# Ethernet.net
KiCad netlist of a schematic drawn in Altium Designer
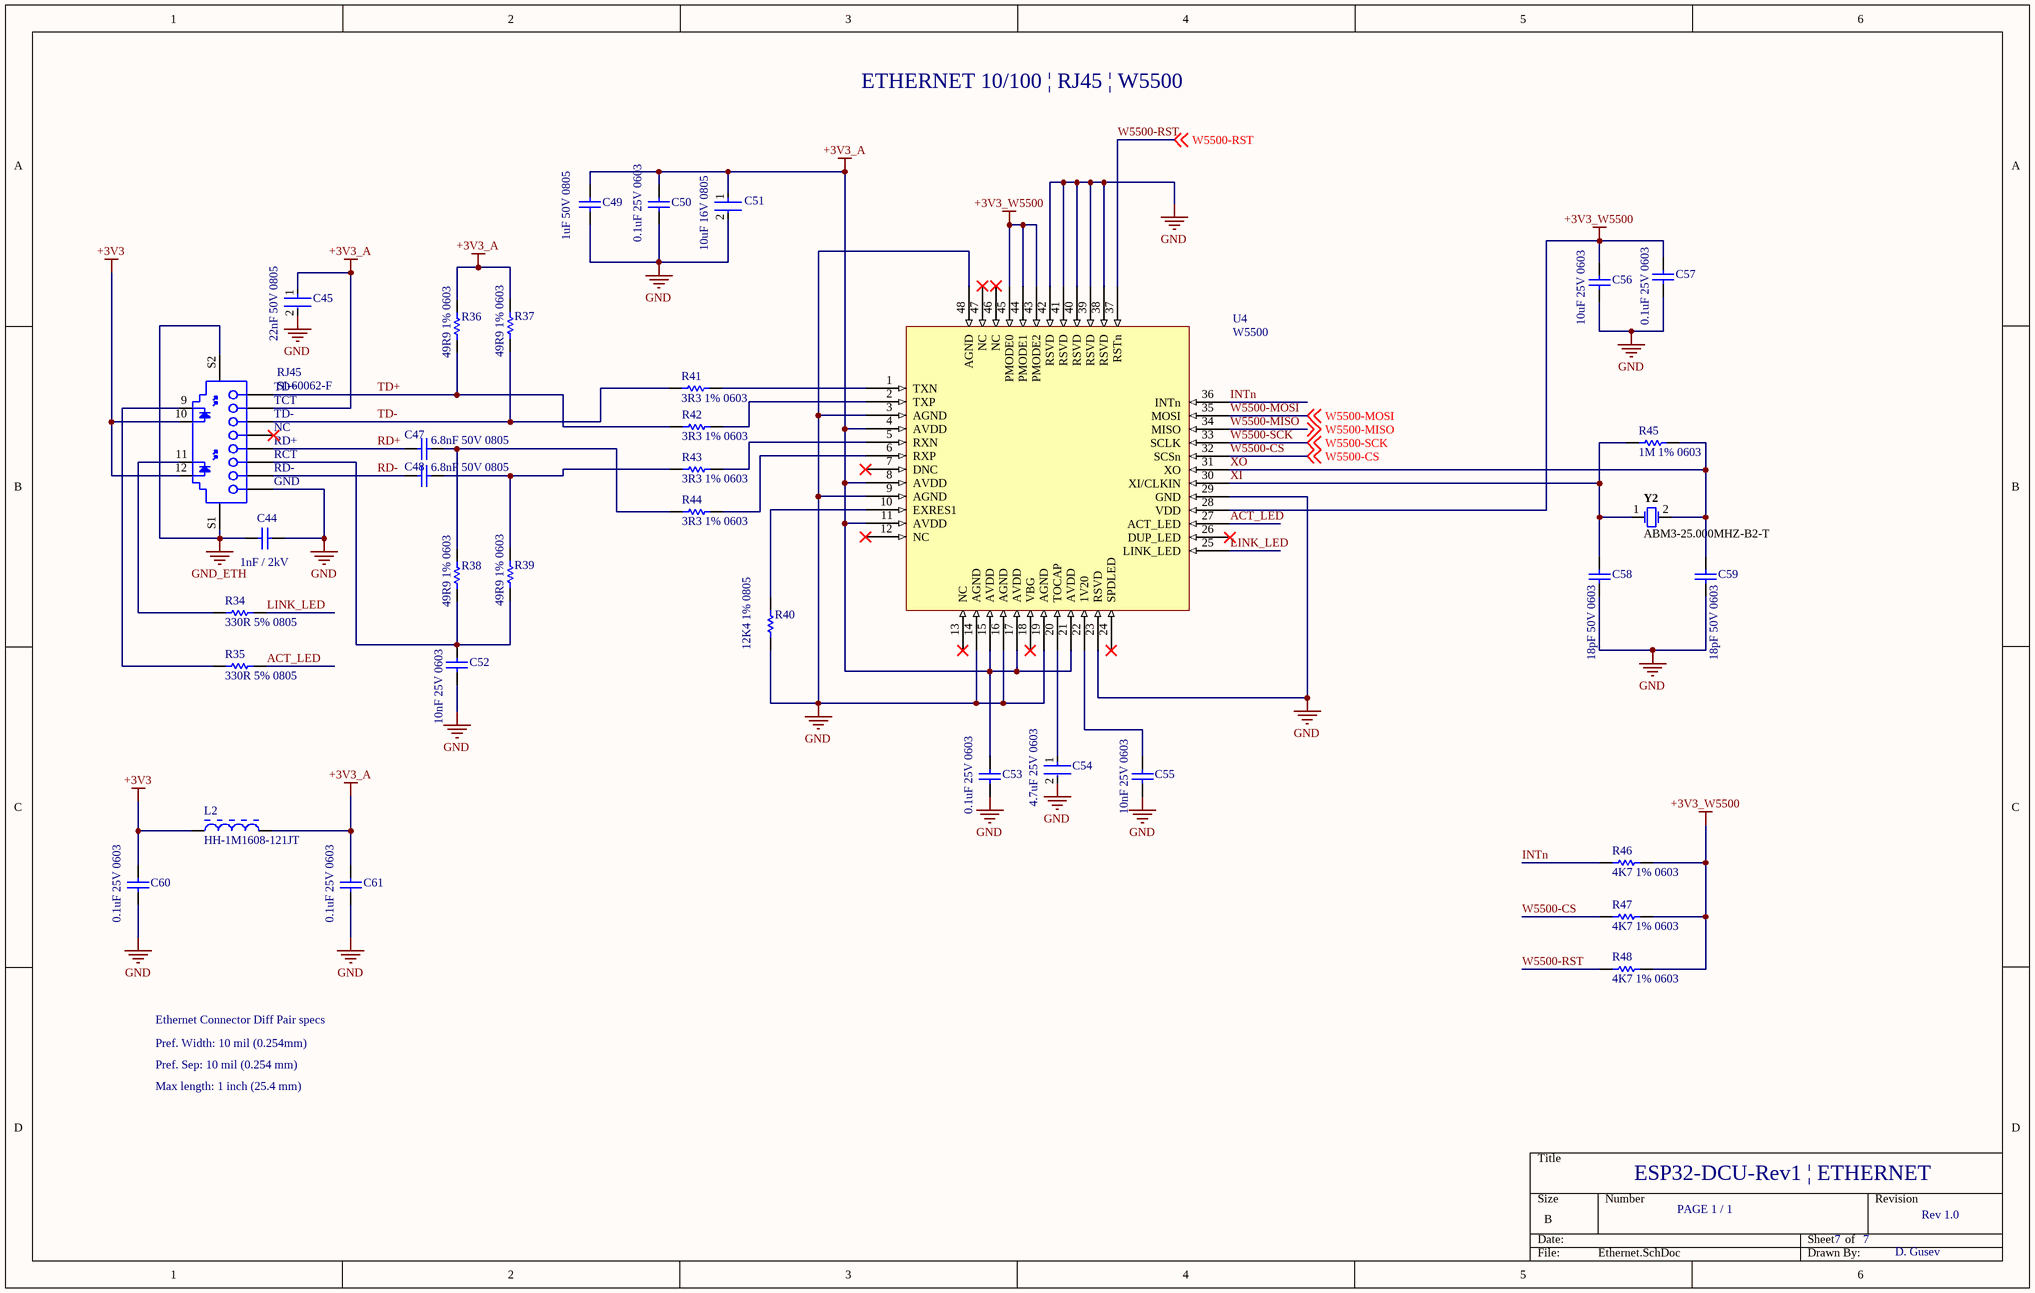
[diagram p0: Ethernet.SchDoc]

(export (version "E")
  (design (tool "Eeschema 10.0.6"))
  (components
    (comp (ref "C44")
      (value "1nF / 2kV")
      (footprint "CAPC4532X155X60LL30T35")
      (description "Chip Capacitor, 1000 pF, +/- 10%, 2000 V, -55 to 125 degC, 1812 (4532 Metric), RoHS, Tape and Reel")
      (fields (field (name "MANUFACTURER") "Kemet") (field (name "TOLERANCE") "±10%"))
      (libsource (lib "Altium Content Vault") (part "CAP-NP-2"))
    )
    (comp (ref "C45")
      (value "22nF 50V 0805")
      (footprint "FP-CL21-IPC_A")
      (description "CL21 Series 0805 22nF 50V ±10% Tolerance X7R Multilayer Ceramic Chip Capacitor")
      (fields (field (name "TOLERANCE") "10%") (field (name "VOLTAGE") "50V"))
      (libsource (lib "Altium Content Vault") (part "b4654b650e69147ec39a6b967a45e02"))
    )
    (comp (ref "C47")
      (value "6.8nF 50V 0805")
      (footprint "CAPC2013X94X50NL20T25")
      (fields
        (field (name "MANUFACTURER") "AVX Interconnect / Elco")
        (field (name "PART NUMBER") "08055C682KAT2A")
      )
      (libsource (lib "Altium Content Vault") (part "CAP"))
    )
    (comp (ref "C48")
      (value "6.8nF 50V 0805")
      (footprint "CAPC2013X94X50NL20T25")
      (fields
        (field (name "MANUFACTURER") "AVX Interconnect / Elco")
        (field (name "PART NUMBER") "08055C682KAT2A")
      )
      (libsource (lib "Altium Content Vault") (part "CAP"))
    )
    (comp (ref "C49")
      (value "1uF 50V 0805")
      (footprint "CAPC2013X135X45LL10T25")
      (fields (field (name "MANUFACTURER") "Murata") (field (name "PART NUMBER") "GRM21BR71H105KA12L"))
      (libsource (lib "Altium Content Vault") (part "CAP"))
    )
    (comp (ref "C50")
      (value "0.1uF 25V 0603")
      (footprint "CAPC1608X90X35LL10T15")
      (fields (field (name "PART NUMBER") "GRM188R71E104KA01D") (field (name "MANUFACTURER") "Murata"))
      (libsource (lib "Altium Content Vault") (part "CAP"))
    )
    (comp (ref "C51")
      (value "10uF 16V 0805")
      (footprint "FP-GRM21B-0_1-IPC_C")
      (description "Chip Multilayer Ceramic Capacitors for General Purpose, 0805, 10uF, X5R, 15%, 10%, 16V")
      (fields (field (name "TOLERANCE") "10%") (field (name "VOLTAGE") "16V"))
      (libsource (lib "Altium Content Vault") (part "b4654b650e69147ec39a6b967a45e02"))
    )
    (comp (ref "C52")
      (value "10nF 25V 0603")
      (footprint "CAPC1608X90X35NL15T15")
      (fields
        (field (name "PART NUMBER") "06033C103KAT2A")
        (field (name "MANUFACTURER") "AVX Interconnect / Elco")
      )
      (libsource (lib "Altium Content Vault") (part "CAP"))
    )
    (comp (ref "C53")
      (value "0.1uF 25V 0603")
      (footprint "CAPC1608X90X35LL10T15")
      (fields (field (name "PART NUMBER") "GRM188R71E104KA01D") (field (name "MANUFACTURER") "Murata"))
      (libsource (lib "Altium Content Vault") (part "CAP"))
    )
    (comp (ref "C54")
      (value "4.7uF 25V 0603")
      (footprint "FP-GRM188-0_15-IPC_C")
      (description "Chip Multilayer Ceramic Capacitors for General Purpose, 0603, 4.7uF, X5R, 15%, 10%, 25V")
      (fields (field (name "VOLTAGE") "25V") (field (name "TOLERANCE") "10%"))
      (libsource (lib "Altium Content Vault") (part "02cd4be3c70576c341d710602a673aa"))
    )
    (comp (ref "C55")
      (value "10nF 25V 0603")
      (footprint "CAPC1608X90X35NL15T15")
      (fields
        (field (name "PART NUMBER") "06033C103KAT2A")
        (field (name "MANUFACTURER") "AVX Interconnect / Elco")
      )
      (libsource (lib "Altium Content Vault") (part "CAP"))
    )
    (comp (ref "C56")
      (value "10uF 25V 0603")
      (footprint "CAPC1608X100X20VL10T10")
      (description "Chip Capacitor, 10 uF, +/- 20%, 25 V, -55 to 85 degC, 0603 (1608 Metric), RoHS, Tape and Reel")
      (fields (field (name "MANUFACTURER") "TDK") (field (name "TOLERANCE") "±20%"))
      (libsource (lib "Altium Content Vault") (part "CAP-NP-2"))
    )
    (comp (ref "C57")
      (value "0.1uF 25V 0603")
      (footprint "CAPC1608X90X35LL10T15")
      (fields (field (name "PART NUMBER") "GRM188R71E104KA01D") (field (name "MANUFACTURER") "Murata"))
      (libsource (lib "Altium Content Vault") (part "CAP"))
    )
    (comp (ref "C58")
      (value "18pF 50V 0603")
      (footprint "CAPC1608X90X40LL10T20")
      (description "Chip Capacitor, 18 pF, +/- 5%, 50 V, -55 to 125 degC, 0603 (1608 Metric), RoHS, Tape and Reel")
      (fields (field (name "TOLERANCE") "1%"))
      (libsource (lib "Altium Content Vault") (part "CAP-NP-2"))
    )
    (comp (ref "C59")
      (value "18pF 50V 0603")
      (footprint "CAPC1608X90X40LL10T20")
      (description "Chip Capacitor, 18 pF, +/- 5%, 50 V, -55 to 125 degC, 0603 (1608 Metric), RoHS, Tape and Reel")
      (fields (field (name "TOLERANCE") "1%"))
      (libsource (lib "Altium Content Vault") (part "CAP-NP-2"))
    )
    (comp (ref "C60")
      (value "0.1uF 25V 0603")
      (footprint "CAPC1608X90X35LL10T15")
      (fields (field (name "PART NUMBER") "GRM188R71E104KA01D") (field (name "MANUFACTURER") "Murata"))
      (libsource (lib "Altium Content Vault") (part "CAP"))
    )
    (comp (ref "C61")
      (value "0.1uF 25V 0603")
      (footprint "CAPC1608X90X35LL10T15")
      (fields (field (name "PART NUMBER") "GRM188R71E104KA01D") (field (name "MANUFACTURER") "Murata"))
      (libsource (lib "Altium Content Vault") (part "CAP"))
    )
    (comp (ref "L2")
      (value "HH-1M1608-121JT")
      (footprint "CTC-1608_L")
      (description "Chip Ferrite Bead, 0.14 Ohm, 1.1 A, -55 to 125 degC, 2-Pin SMD, RoHS, Tape and Reel")
      (fields (field (name "MANUFACTURER") "CTC Coils") (field (name "PARTNUMBER") "HH-1M1608"))
      (libsource (lib "Altium Content Vault") (part "IND-FB-2"))
    )
    (comp (ref "R34")
      (value "330R 5% 0805")
      (footprint "RESC2013X60X35LL10T20")
      (description "Chip Resistor, 330 Ohm, +/- 1%, 125 mW, -55 to 155 degC, 0805 (2012 Metric), RoHS, Tape and Reel")
      (fields (field (name "MANUFACTURER") "Yageo") (field (name "TOLERANCE") "1%"))
      (libsource (lib "Altium Content Vault") (part "RES-2"))
    )
    (comp (ref "R35")
      (value "330R 5% 0805")
      (footprint "RESC2013X60X35LL10T20")
      (description "Chip Resistor, 330 Ohm, +/- 1%, 125 mW, -55 to 155 degC, 0805 (2012 Metric), RoHS, Tape and Reel")
      (fields (field (name "MANUFACTURER") "Yageo") (field (name "TOLERANCE") "1%"))
      (libsource (lib "Altium Content Vault") (part "RES-2"))
    )
    (comp (ref "R36")
      (value "49R9 1% 0603")
      (footprint "RESC1608X55X25NL10T15")
      (libsource (lib "Altium Content Vault") (part "RES-2"))
    )
    (comp (ref "R37")
      (value "49R9 1% 0603")
      (footprint "RESC1608X55X25NL10T15")
      (libsource (lib "Altium Content Vault") (part "RES-2"))
    )
    (comp (ref "R38")
      (value "49R9 1% 0603")
      (footprint "RESC1608X55X25NL10T15")
      (libsource (lib "Altium Content Vault") (part "RES-2"))
    )
    (comp (ref "R39")
      (value "49R9 1% 0603")
      (footprint "RESC1608X55X25NL10T15")
      (libsource (lib "Altium Content Vault") (part "RES-2"))
    )
    (comp (ref "R40")
      (value "12K4 1% 0805")
      (footprint "RESC2013X60X35NL10T20")
      (fields (field (name "PART NUMBER") "RC0805FR-0712K4L") (field (name "MANUFACTURER") "Yageo"))
      (libsource (lib "Altium Content Vault") (part "RES"))
    )
    (comp (ref "R41")
      (value "3R3 1% 0603")
      (footprint "RESC1608X55X25ML10T15")
      (fields (field (name "PART NUMBER") "RC0603JR-073R3L") (field (name "MANUFACTURER") "Yageo"))
      (libsource (lib "Altium Content Vault") (part "RES"))
    )
    (comp (ref "R42")
      (value "3R3 1% 0603")
      (footprint "RESC1608X55X25ML10T15")
      (fields (field (name "PART NUMBER") "RC0603JR-073R3L") (field (name "MANUFACTURER") "Yageo"))
      (libsource (lib "Altium Content Vault") (part "RES"))
    )
    (comp (ref "R43")
      (value "3R3 1% 0603")
      (footprint "RESC1608X55X25ML10T15")
      (fields (field (name "PART NUMBER") "RC0603JR-073R3L") (field (name "MANUFACTURER") "Yageo"))
      (libsource (lib "Altium Content Vault") (part "RES"))
    )
    (comp (ref "R44")
      (value "3R3 1% 0603")
      (footprint "RESC1608X55X25ML10T15")
      (fields (field (name "PART NUMBER") "RC0603JR-073R3L") (field (name "MANUFACTURER") "Yageo"))
      (libsource (lib "Altium Content Vault") (part "RES"))
    )
    (comp (ref "R45")
      (value "1M 1% 0603")
      (footprint "RESC1608X55X25LL10T15")
      (fields (field (name "MANUFACTURER") "Yageo") (field (name "PART NUMBER") "AC0603FR-071ML"))
      (libsource (lib "Altium Content Vault") (part "RES"))
    )
    (comp (ref "R46")
      (value "4K7 1% 0603")
      (footprint "RESC1608X55X25LL10T15")
      (description "Chip Resistor, 4.7 KOhm, +/- 1%, 0.1 W, -55 to 155 degC, 0603 (1608 Metric), RoHS, Tape and Reel")
      (fields (field (name "MANUFACTURER") "Yageo") (field (name "TOLERANCE") "1%"))
      (libsource (lib "Altium Content Vault") (part "RES-2"))
    )
    (comp (ref "R47")
      (value "4K7 1% 0603")
      (footprint "RESC1608X55X25LL10T15")
      (description "Chip Resistor, 4.7 KOhm, +/- 1%, 0.1 W, -55 to 155 degC, 0603 (1608 Metric), RoHS, Tape and Reel")
      (fields (field (name "MANUFACTURER") "Yageo") (field (name "TOLERANCE") "1%"))
      (libsource (lib "Altium Content Vault") (part "RES-2"))
    )
    (comp (ref "R48")
      (value "4K7 1% 0603")
      (footprint "RESC1608X55X25LL10T15")
      (description "Chip Resistor, 4.7 KOhm, +/- 1%, 0.1 W, -55 to 155 degC, 0603 (1608 Metric), RoHS, Tape and Reel")
      (fields (field (name "MANUFACTURER") "Yageo") (field (name "TOLERANCE") "1%"))
      (libsource (lib "Altium Content Vault") (part "RES-2"))
    )
    (comp (ref "RJ45")
      (value "SI-60062-F")
      (footprint "BELF-SI-60062-F_V")
      (description "1 Port RJ45 Magjack Connector with Yellow and Green LED, 10/100 Base-T, 12-Pin THD, RoHS, Tray")
      (fields (field (name "MANUFACTURER") "Bel Fuse"))
      (libsource (lib "Altium Content Vault") (part "RJ45-12-2SHLD"))
    )
    (comp (ref "U4")
      (value "W5500")
      (footprint "W5500")
      (description "W5500 10/100 ETHERNET")
      (libsource (lib "ESP32-DCU-Rev1") (part "W5500"))
    )
    (comp (ref "Y2")
      (value "ABM3-25.000MHZ-B2-T")
      (footprint "ABRA-ABM3_V")
      (description "Miniature Ceramic Crystal, 25 MHz, +/- 20 ppm, -20 to 70 degC, 2-Pin SMD, RoHS, Tape and Reel")
      (fields (field (name "TOLERANCE") "20PPM") (field (name "MANUFACTURER") "ABRACON"))
      (libsource (lib "Altium Content Vault") (part "XTAL-1-2-2"))
    )
  )
  (nets
    (net (code "1") (name "+3V3") (class "Default")
      (node (ref "C60") (pin "2") (pinfunction "2_2") (pintype "passive"))
      (node (ref "L2") (pin "1") (pinfunction "1_1") (pintype "passive"))
      (node (ref "RJ45") (pin "10") (pinfunction "10_10") (pintype "passive"))
      (node (ref "RJ45") (pin "12") (pinfunction "12_12") (pintype "passive"))
    )
    (net (code "2") (name "+3V3_A") (class "Default")
      (node (ref "C45") (pin "1") (pinfunction "1_1") (pintype "passive"))
      (node (ref "C49") (pin "2") (pinfunction "2_2") (pintype "passive"))
      (node (ref "C50") (pin "2") (pinfunction "2_2") (pintype "passive"))
      (node (ref "C51") (pin "1") (pinfunction "1_1") (pintype "passive"))
      (node (ref "C53") (pin "2") (pinfunction "2_2") (pintype "passive"))
      (node (ref "C61") (pin "2") (pinfunction "2_2") (pintype "passive"))
      (node (ref "L2") (pin "2") (pinfunction "2_2") (pintype "passive"))
      (node (ref "R36") (pin "2") (pinfunction "2_2") (pintype "passive"))
      (node (ref "R37") (pin "2") (pinfunction "2_2") (pintype "passive"))
      (node (ref "RJ45") (pin "2") (pinfunction "TCT_2") (pintype "passive"))
      (node (ref "U4") (pin "11") (pinfunction "AVDD_11") (pintype "input"))
      (node (ref "U4") (pin "15") (pinfunction "AVDD_15") (pintype "input"))
      (node (ref "U4") (pin "17") (pinfunction "AVDD_17") (pintype "input"))
      (node (ref "U4") (pin "21") (pinfunction "AVDD_21") (pintype "input"))
      (node (ref "U4") (pin "4") (pinfunction "AVDD_4") (pintype "input"))
      (node (ref "U4") (pin "8") (pinfunction "AVDD_8") (pintype "input"))
    )
    (net (code "3") (name "+3V3_W5500") (class "Default")
      (node (ref "C56") (pin "2") (pinfunction "2_2") (pintype "passive"))
      (node (ref "C57") (pin "2") (pinfunction "2_2") (pintype "passive"))
      (node (ref "R46") (pin "2") (pinfunction "2_2") (pintype "passive"))
      (node (ref "R47") (pin "2") (pinfunction "2_2") (pintype "passive"))
      (node (ref "R48") (pin "2") (pinfunction "2_2") (pintype "passive"))
      (node (ref "U4") (pin "28") (pinfunction "VDD_28") (pintype "input"))
      (node (ref "U4") (pin "43") (pinfunction "PMODE2_43") (pintype "input"))
      (node (ref "U4") (pin "44") (pinfunction "PMODE1_44") (pintype "input"))
      (node (ref "U4") (pin "45") (pinfunction "PMODE0_45") (pintype "input"))
    )
    (net (code "4") (name "/ACT_LED") (class "Default")
      (node (ref "R35") (pin "2") (pinfunction "2_2") (pintype "passive"))
      (node (ref "U4") (pin "27") (pinfunction "ACT_LED_27") (pintype "input"))
    )
    (net (code "5") (name "/INTn") (class "Default")
      (node (ref "R46") (pin "1") (pinfunction "1_1") (pintype "passive"))
      (node (ref "U4") (pin "36") (pinfunction "INTn_36") (pintype "input"))
    )
    (net (code "6") (name "/LINK_LED") (class "Default")
      (node (ref "R34") (pin "2") (pinfunction "2_2") (pintype "passive"))
      (node (ref "U4") (pin "25") (pinfunction "LINK_LED_25") (pintype "input"))
    )
    (net (code "7") (name "/RD+") (class "Default")
      (node (ref "C47") (pin "1") (pinfunction "1_1") (pintype "passive"))
      (node (ref "RJ45") (pin "5") (pinfunction "RD+_5") (pintype "passive"))
    )
    (net (code "8") (name "/RD-") (class "Default")
      (node (ref "C48") (pin "1") (pinfunction "1_1") (pintype "passive"))
      (node (ref "RJ45") (pin "7") (pinfunction "RD-_7") (pintype "passive"))
    )
    (net (code "9") (name "/TD+") (class "Default")
      (node (ref "R36") (pin "1") (pinfunction "1_1") (pintype "passive"))
      (node (ref "R42") (pin "1") (pinfunction "1_1") (pintype "passive"))
      (node (ref "RJ45") (pin "1") (pinfunction "TD+_1") (pintype "passive"))
    )
    (net (code "10") (name "/TD-") (class "Default")
      (node (ref "R37") (pin "1") (pinfunction "1_1") (pintype "passive"))
      (node (ref "R41") (pin "1") (pinfunction "1_1") (pintype "passive"))
      (node (ref "RJ45") (pin "3") (pinfunction "TD-_3") (pintype "passive"))
    )
    (net (code "11") (name "/XI") (class "Default")
      (node (ref "C58") (pin "2") (pinfunction "2_2") (pintype "passive"))
      (node (ref "R45") (pin "1") (pinfunction "1_1") (pintype "passive"))
      (node (ref "U4") (pin "30") (pinfunction "XI/CLKIN_30") (pintype "input"))
      (node (ref "Y2") (pin "1") (pinfunction "1_1") (pintype "passive"))
    )
    (net (code "12") (name "/XO") (class "Default")
      (node (ref "C59") (pin "2") (pinfunction "2_2") (pintype "passive"))
      (node (ref "R45") (pin "2") (pinfunction "2_2") (pintype "passive"))
      (node (ref "U4") (pin "31") (pinfunction "XO_31") (pintype "input"))
      (node (ref "Y2") (pin "2") (pinfunction "2_2") (pintype "passive"))
    )
    (net (code "13") (name "GND") (class "Default")
      (node (ref "C44") (pin "2") (pinfunction "2_2") (pintype "passive"))
      (node (ref "C45") (pin "2") (pinfunction "2_2") (pintype "passive"))
      (node (ref "C49") (pin "1") (pinfunction "1_1") (pintype "passive"))
      (node (ref "C50") (pin "1") (pinfunction "1_1") (pintype "passive"))
      (node (ref "C51") (pin "2") (pinfunction "2_2") (pintype "passive"))
      (node (ref "C52") (pin "1") (pinfunction "1_1") (pintype "passive"))
      (node (ref "C53") (pin "1") (pinfunction "1_1") (pintype "passive"))
      (node (ref "C54") (pin "2") (pinfunction "2_2") (pintype "passive"))
      (node (ref "C55") (pin "1") (pinfunction "1_1") (pintype "passive"))
      (node (ref "C56") (pin "1") (pinfunction "1_1") (pintype "passive"))
      (node (ref "C57") (pin "1") (pinfunction "1_1") (pintype "passive"))
      (node (ref "C58") (pin "1") (pinfunction "1_1") (pintype "passive"))
      (node (ref "C59") (pin "1") (pinfunction "1_1") (pintype "passive"))
      (node (ref "C60") (pin "1") (pinfunction "1_1") (pintype "passive"))
      (node (ref "C61") (pin "1") (pinfunction "1_1") (pintype "passive"))
      (node (ref "R40") (pin "1") (pinfunction "1_1") (pintype "passive"))
      (node (ref "RJ45") (pin "8") (pinfunction "GND_8") (pintype "passive"))
      (node (ref "U4") (pin "14") (pinfunction "AGND_14") (pintype "input"))
      (node (ref "U4") (pin "16") (pinfunction "AGND_16") (pintype "input"))
      (node (ref "U4") (pin "19") (pinfunction "AGND_19") (pintype "input"))
      (node (ref "U4") (pin "23") (pinfunction "RSVD_23") (pintype "input"))
      (node (ref "U4") (pin "29") (pinfunction "GND_29") (pintype "input"))
      (node (ref "U4") (pin "3") (pinfunction "AGND_3") (pintype "input"))
      (node (ref "U4") (pin "38") (pinfunction "RSVD_38") (pintype "input"))
      (node (ref "U4") (pin "39") (pinfunction "RSVD_39") (pintype "input"))
      (node (ref "U4") (pin "40") (pinfunction "RSVD_40") (pintype "input"))
      (node (ref "U4") (pin "41") (pinfunction "RSVD_41") (pintype "input"))
      (node (ref "U4") (pin "42") (pinfunction "RSVD_42") (pintype "input"))
      (node (ref "U4") (pin "48") (pinfunction "AGND_48") (pintype "input"))
      (node (ref "U4") (pin "9") (pinfunction "AGND_9") (pintype "input"))
    )
    (net (code "14") (name "GND_ETH") (class "Default")
      (node (ref "C44") (pin "1") (pinfunction "1_1") (pintype "passive"))
      (node (ref "RJ45") (pin "S1") (pinfunction "S1_S1") (pintype "passive"))
      (node (ref "RJ45") (pin "S2") (pinfunction "S2_S2") (pintype "passive"))
    )
    (net (code "15") (name "Net-(C47-Pad2)") (class "Default")
      (node (ref "C47") (pin "2") (pinfunction "2_2") (pintype "passive"))
      (node (ref "R38") (pin "2") (pinfunction "2_2") (pintype "passive"))
      (node (ref "R44") (pin "1") (pinfunction "1_1") (pintype "passive"))
    )
    (net (code "16") (name "Net-(C48-Pad2)") (class "Default")
      (node (ref "C48") (pin "2") (pinfunction "2_2") (pintype "passive"))
      (node (ref "R39") (pin "2") (pinfunction "2_2") (pintype "passive"))
      (node (ref "R43") (pin "1") (pinfunction "1_1") (pintype "passive"))
    )
    (net (code "17") (name "Net-(R34-Pad1)") (class "Default")
      (node (ref "R34") (pin "1") (pinfunction "1_1") (pintype "passive"))
      (node (ref "RJ45") (pin "11") (pinfunction "11_11") (pintype "passive"))
    )
    (net (code "18") (name "Net-(R35-Pad1)") (class "Default")
      (node (ref "R35") (pin "1") (pinfunction "1_1") (pintype "passive"))
      (node (ref "RJ45") (pin "9") (pinfunction "9_9") (pintype "passive"))
    )
    (net (code "19") (name "Net-(RJ45-RCT)") (class "Default")
      (node (ref "C52") (pin "2") (pinfunction "2_2") (pintype "passive"))
      (node (ref "R38") (pin "1") (pinfunction "1_1") (pintype "passive"))
      (node (ref "R39") (pin "1") (pinfunction "1_1") (pintype "passive"))
      (node (ref "RJ45") (pin "6") (pinfunction "RCT_6") (pintype "passive"))
    )
    (net (code "20") (name "Net-(U4-1V20)") (class "Default")
      (node (ref "C55") (pin "2") (pinfunction "2_2") (pintype "passive"))
      (node (ref "U4") (pin "22") (pinfunction "1V20_22") (pintype "input"))
    )
    (net (code "21") (name "Net-(U4-EXRES1)") (class "Default")
      (node (ref "R40") (pin "2") (pinfunction "2_2") (pintype "passive"))
      (node (ref "U4") (pin "10") (pinfunction "EXRES1_10") (pintype "input"))
    )
    (net (code "22") (name "Net-(U4-RXN)") (class "Default")
      (node (ref "R43") (pin "2") (pinfunction "2_2") (pintype "passive"))
      (node (ref "U4") (pin "5") (pinfunction "RXN_5") (pintype "input"))
    )
    (net (code "23") (name "Net-(U4-RXP)") (class "Default")
      (node (ref "R44") (pin "2") (pinfunction "2_2") (pintype "passive"))
      (node (ref "U4") (pin "6") (pinfunction "RXP_6") (pintype "input"))
    )
    (net (code "24") (name "Net-(U4-TOCAP)") (class "Default")
      (node (ref "C54") (pin "1") (pinfunction "1_1") (pintype "passive"))
      (node (ref "U4") (pin "20") (pinfunction "TOCAP_20") (pintype "input"))
    )
    (net (code "25") (name "Net-(U4-TXN)") (class "Default")
      (node (ref "R41") (pin "2") (pinfunction "2_2") (pintype "passive"))
      (node (ref "U4") (pin "1") (pinfunction "TXN_1") (pintype "input"))
    )
    (net (code "26") (name "Net-(U4-TXP)") (class "Default")
      (node (ref "R42") (pin "2") (pinfunction "2_2") (pintype "passive"))
      (node (ref "U4") (pin "2") (pinfunction "TXP_2") (pintype "input"))
    )
    (net (code "27") (name "W5500-CS") (class "Default")
      (node (ref "R47") (pin "1") (pinfunction "1_1") (pintype "passive"))
      (node (ref "U4") (pin "32") (pinfunction "SCSn_32") (pintype "input"))
    )
    (net (code "28") (name "W5500-MISO") (class "Default")
      (node (ref "U4") (pin "34") (pinfunction "MISO_34") (pintype "input"))
    )
    (net (code "29") (name "W5500-MOSI") (class "Default")
      (node (ref "U4") (pin "35") (pinfunction "MOSI_35") (pintype "input"))
    )
    (net (code "30") (name "W5500-RST") (class "Default")
      (node (ref "R48") (pin "1") (pinfunction "1_1") (pintype "passive"))
      (node (ref "U4") (pin "37") (pinfunction "RSTn_37") (pintype "input"))
    )
    (net (code "31") (name "W5500-SCK") (class "Default")
      (node (ref "U4") (pin "33") (pinfunction "SCLK_33") (pintype "input"))
    )
    (net (code "32") (name "unconnected-(RJ45-NC-Pad4)") (class "Default")
      (node (ref "RJ45") (pin "4") (pinfunction "NC_4") (pintype "passive+no_connect"))
    )
    (net (code "33") (name "unconnected-(U4-DNC-Pad7)") (class "Default")
      (node (ref "U4") (pin "7") (pinfunction "DNC_7") (pintype "input+no_connect"))
    )
    (net (code "34") (name "unconnected-(U4-DUP_LED-Pad26)") (class "Default")
      (node (ref "U4") (pin "26") (pinfunction "DUP_LED_26") (pintype "input+no_connect"))
    )
    (net (code "35") (name "unconnected-(U4-NC-Pad12)") (class "Default")
      (node (ref "U4") (pin "12") (pinfunction "NC_12") (pintype "input+no_connect"))
    )
    (net (code "36") (name "unconnected-(U4-NC-Pad13)") (class "Default")
      (node (ref "U4") (pin "13") (pinfunction "NC_13") (pintype "input+no_connect"))
    )
    (net (code "37") (name "unconnected-(U4-NC-Pad46)") (class "Default")
      (node (ref "U4") (pin "46") (pinfunction "NC_46") (pintype "input+no_connect"))
    )
    (net (code "38") (name "unconnected-(U4-NC-Pad47)") (class "Default")
      (node (ref "U4") (pin "47") (pinfunction "NC_47") (pintype "input+no_connect"))
    )
    (net (code "39") (name "unconnected-(U4-SPDLED-Pad24)") (class "Default")
      (node (ref "U4") (pin "24") (pinfunction "SPDLED_24") (pintype "input+no_connect"))
    )
    (net (code "40") (name "unconnected-(U4-VBG-Pad18)") (class "Default")
      (node (ref "U4") (pin "18") (pinfunction "VBG_18") (pintype "input+no_connect"))
    )
  )
)
